# interconnect_RSS_V1_0.net
KiCad netlist of a schematic drawn in EAGLE
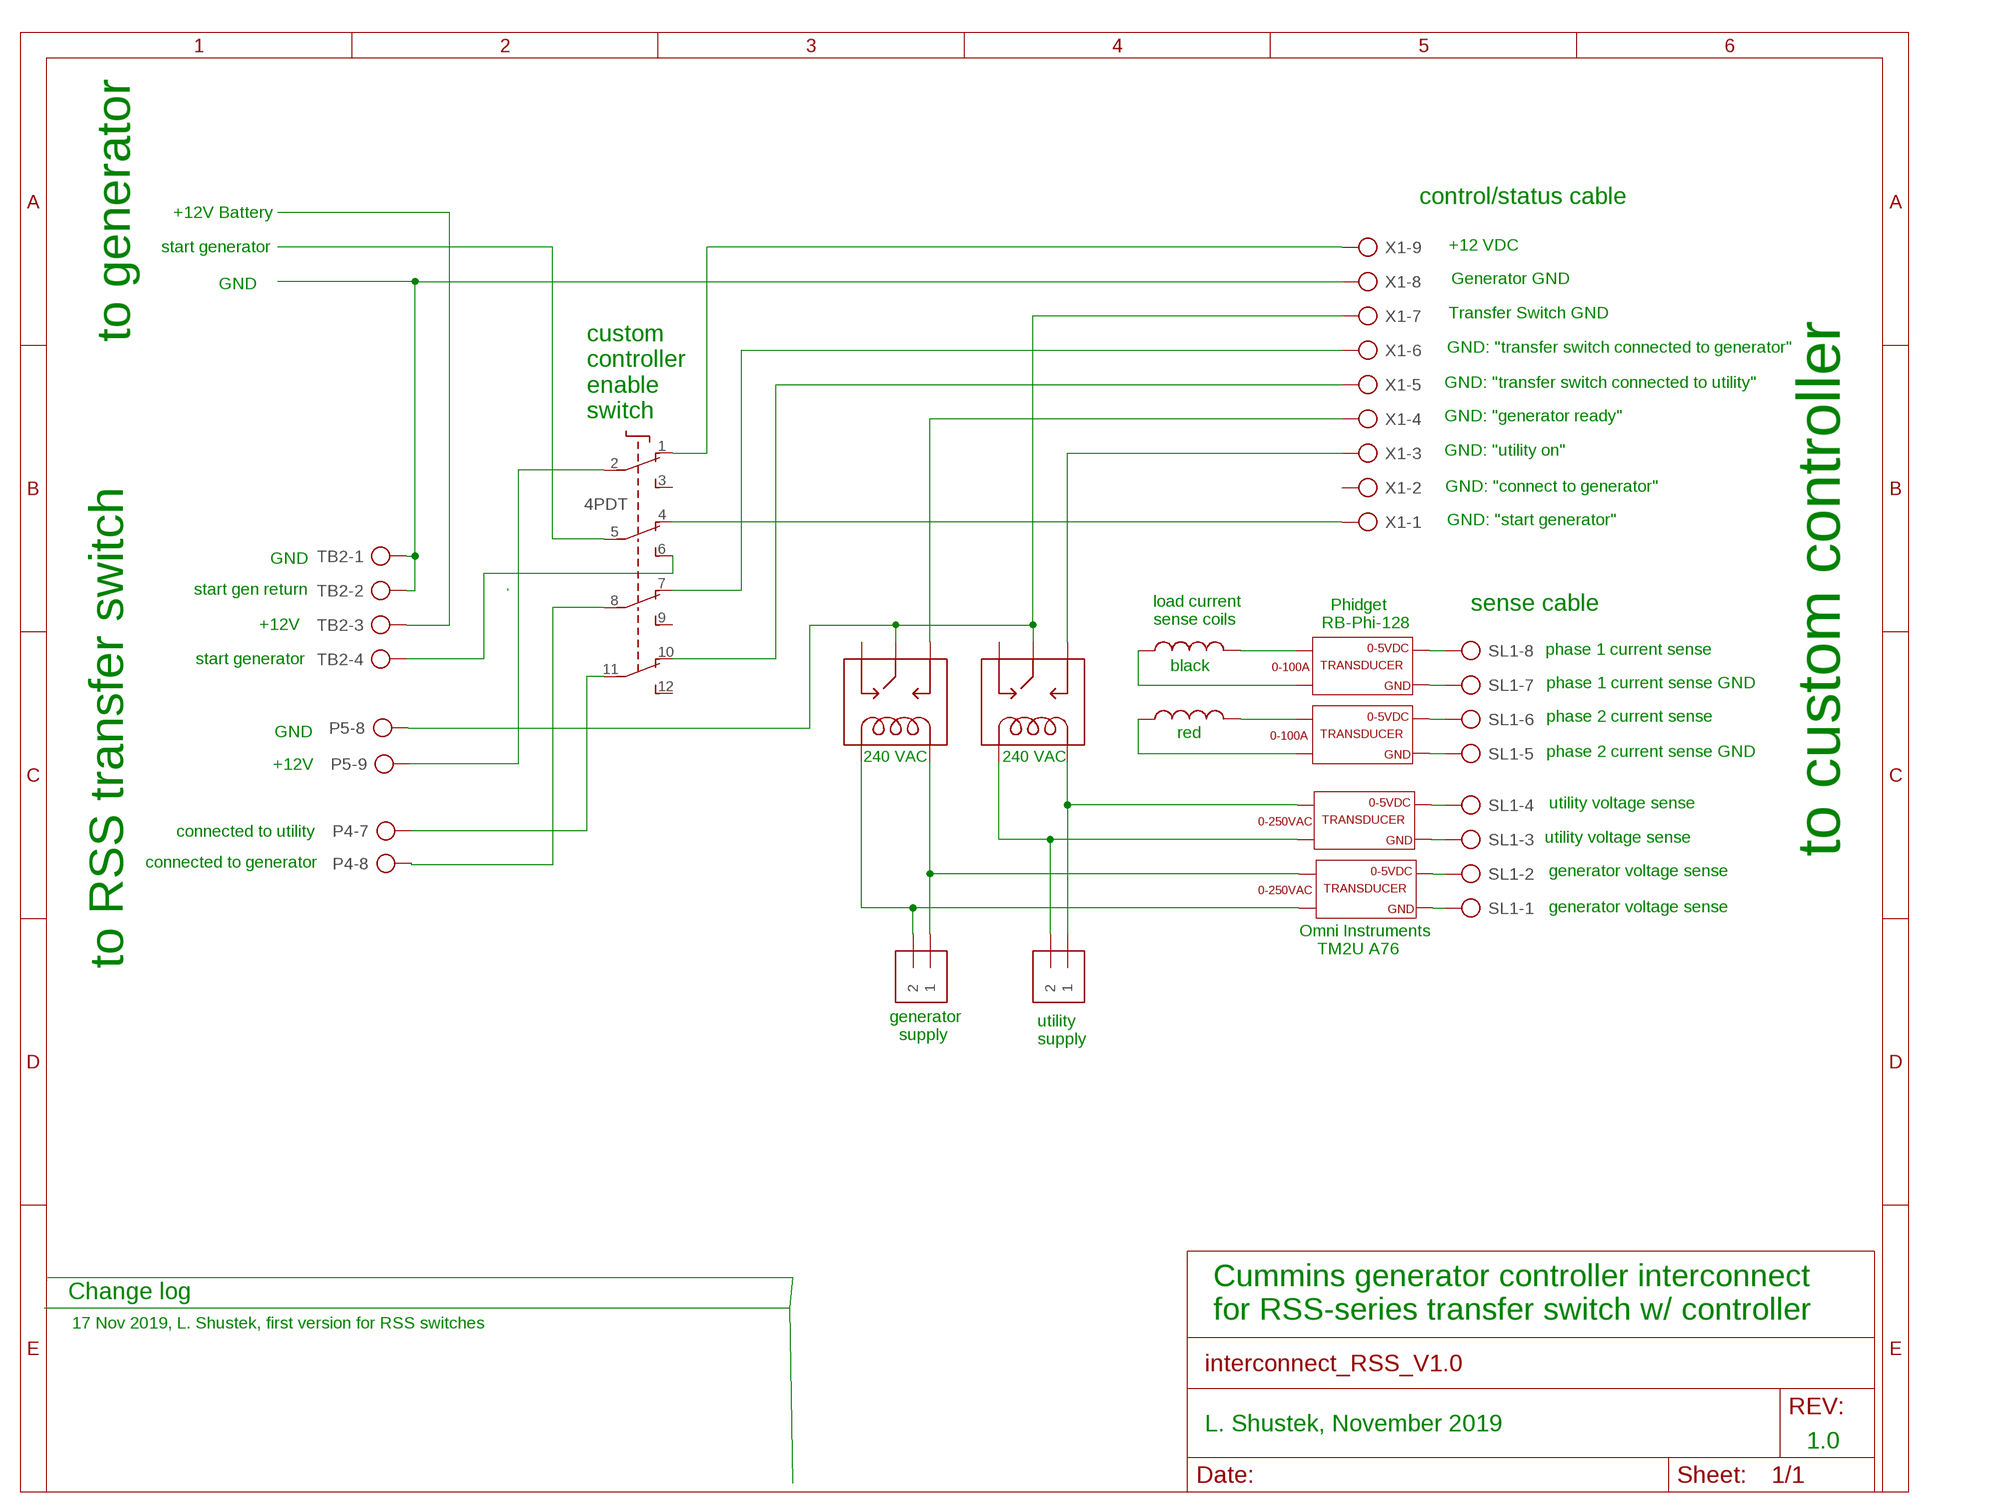
[diagram p0: schematic, sheet 1]

(export (version "E")
  (design (tool "Eeschema 10.0.6"))
  (components
    (comp (ref "J1")
      (value "1X2-3.5MM")
      (footprint "eagle-import:1X2-3.5MM")
      (libsource (lib "eagle-import") (part "1X2-3.5MM"))
    )
    (comp (ref "J2")
      (value "1X2-3.5MM")
      (footprint "eagle-import:1X2-3.5MM")
      (libsource (lib "eagle-import") (part "1X2-3.5MM"))
    )
    (comp (ref "K1")
      (value "RELAY-SPDT-V2")
      (footprint "eagle-import:RELAY-PANASONIC-JS")
      (libsource (lib "eagle-import") (part "RELAY-SPDT-V2"))
    )
    (comp (ref "K2")
      (value "RELAY-SPDT-V2")
      (footprint "eagle-import:RELAY-PANASONIC-JS")
      (libsource (lib "eagle-import") (part "RELAY-SPDT-V2"))
    )
    (comp (ref "L1")
      (value "L-US0204/5")
      (footprint "eagle-import:0204_5")
      (libsource (lib "eagle-import") (part "L-US0204/5"))
    )
    (comp (ref "L2")
      (value "L-US0204/5")
      (footprint "eagle-import:0204_5")
      (libsource (lib "eagle-import") (part "L-US0204/5"))
    )
    (comp (ref "P4")
      (value "AK500/10")
      (footprint "eagle-import:AK500_10")
      (libsource (lib "eagle-import") (part "AK500/10"))
    )
    (comp (ref "P5")
      (value "AK500/10")
      (footprint "eagle-import:AK500_10")
      (libsource (lib "eagle-import") (part "AK500/10"))
    )
    (comp (ref "S2")
      (value "4PDT")
      (footprint "eagle-import:4PDT")
      (libsource (lib "eagle-import") (part "4PDT"))
    )
    (comp (ref "SL1")
      (value "AK500/8")
      (footprint "eagle-import:AK500_8")
      (libsource (lib "eagle-import") (part "AK500/8"))
    )
    (comp (ref "TB2")
      (value "AK500/10")
      (footprint "eagle-import:AK500_10")
      (libsource (lib "eagle-import") (part "AK500/10"))
    )
    (comp (ref "U$1")
      (value "0-100A")
      (footprint "eagle-import:TRANSDUCER")
      (libsource (lib "eagle-import") (part "TRANSDUCER"))
    )
    (comp (ref "U$2")
      (value "0-100A")
      (footprint "eagle-import:TRANSDUCER")
      (libsource (lib "eagle-import") (part "TRANSDUCER"))
    )
    (comp (ref "U$3")
      (value "0-250VAC")
      (footprint "eagle-import:TRANSDUCER")
      (libsource (lib "eagle-import") (part "TRANSDUCER"))
    )
    (comp (ref "U$4")
      (value "0-250VAC")
      (footprint "eagle-import:TRANSDUCER")
      (libsource (lib "eagle-import") (part "TRANSDUCER"))
    )
    (comp (ref "X1")
      (value "AK500/9")
      (footprint "eagle-import:AK500_9")
      (libsource (lib "eagle-import") (part "AK500/9"))
    )
  )
  (nets
    (net (code "1") (name "Net-(K1-COIL1)") (class "Default")
      (node (ref "J1") (pin "2") (pinfunction "2_2") (pintype "passive"))
      (node (ref "K1") (pin "P$2") (pinfunction "COIL1_P$2") (pintype "bidirectional"))
      (node (ref "U$4") (pin "P$2") (pinfunction "P$2_P$2") (pintype "bidirectional"))
    )
    (net (code "2") (name "Net-(K1-COIL2)") (class "Default")
      (node (ref "J1") (pin "1") (pinfunction "1_1") (pintype "passive"))
      (node (ref "K1") (pin "P$5") (pinfunction "COIL2_P$5") (pintype "bidirectional"))
      (node (ref "U$4") (pin "P$1") (pinfunction "P$1_P$1") (pintype "bidirectional"))
    )
    (net (code "3") (name "Net-(K1-MAIN)") (class "Default")
      (node (ref "K1") (pin "P$1") (pinfunction "MAIN_P$1") (pintype "bidirectional"))
      (node (ref "K2") (pin "P$1") (pinfunction "MAIN_P$1") (pintype "bidirectional"))
      (node (ref "P5") (pin "8") (pinfunction "KL_8") (pintype "passive"))
      (node (ref "X1") (pin "7") (pinfunction "KL_7") (pintype "passive"))
    )
    (net (code "4") (name "Net-(K1-NO)") (class "Default")
      (node (ref "K1") (pin "P$3") (pinfunction "NO_P$3") (pintype "bidirectional"))
      (node (ref "X1") (pin "4") (pinfunction "KL_4") (pintype "passive"))
    )
    (net (code "5") (name "Net-(K2-COIL1)") (class "Default")
      (node (ref "J2") (pin "2") (pinfunction "2_2") (pintype "passive"))
      (node (ref "K2") (pin "P$2") (pinfunction "COIL1_P$2") (pintype "bidirectional"))
      (node (ref "U$3") (pin "P$2") (pinfunction "P$2_P$2") (pintype "bidirectional"))
    )
    (net (code "6") (name "Net-(K2-COIL2)") (class "Default")
      (node (ref "J2") (pin "1") (pinfunction "1_1") (pintype "passive"))
      (node (ref "K2") (pin "P$5") (pinfunction "COIL2_P$5") (pintype "bidirectional"))
      (node (ref "U$3") (pin "P$1") (pinfunction "P$1_P$1") (pintype "bidirectional"))
    )
    (net (code "7") (name "Net-(K2-NO)") (class "Default")
      (node (ref "K2") (pin "P$3") (pinfunction "NO_P$3") (pintype "bidirectional"))
      (node (ref "X1") (pin "3") (pinfunction "KL_3") (pintype "passive"))
    )
    (net (code "8") (name "Net-(L1-Pad1)") (class "Default")
      (node (ref "L1") (pin "1") (pinfunction "1_1") (pintype "passive"))
      (node (ref "U$1") (pin "P$2") (pinfunction "P$2_P$2") (pintype "bidirectional"))
    )
    (net (code "9") (name "Net-(L1-Pad2)") (class "Default")
      (node (ref "L1") (pin "2") (pinfunction "2_2") (pintype "passive"))
      (node (ref "U$1") (pin "P$1") (pinfunction "P$1_P$1") (pintype "bidirectional"))
    )
    (net (code "10") (name "Net-(L2-Pad1)") (class "Default")
      (node (ref "L2") (pin "1") (pinfunction "1_1") (pintype "passive"))
      (node (ref "U$2") (pin "P$2") (pinfunction "P$2_P$2") (pintype "bidirectional"))
    )
    (net (code "11") (name "Net-(L2-Pad2)") (class "Default")
      (node (ref "L2") (pin "2") (pinfunction "2_2") (pintype "passive"))
      (node (ref "U$2") (pin "P$1") (pinfunction "P$1_P$1") (pintype "bidirectional"))
    )
    (net (code "12") (name "Net-(P4H-KL)") (class "Default")
      (node (ref "P4") (pin "7") (pinfunction "KL_7") (pintype "passive"))
      (node (ref "S2") (pin "11") (pinfunction "P4_11") (pintype "passive"))
    )
    (net (code "13") (name "Net-(P4I-KL)") (class "Default")
      (node (ref "P4") (pin "8") (pinfunction "KL_8") (pintype "passive"))
      (node (ref "S2") (pin "8") (pinfunction "P3_8") (pintype "passive"))
    )
    (net (code "14") (name "Net-(P5J-KL)") (class "Default")
      (node (ref "P5") (pin "9") (pinfunction "KL_9") (pintype "passive"))
      (node (ref "S2") (pin "2") (pinfunction "P1_2") (pintype "passive"))
    )
    (net (code "15") (name "Net-(S2-O1)") (class "Default")
      (node (ref "S2") (pin "1") (pinfunction "O1_1") (pintype "passive"))
      (node (ref "X1") (pin "9") (pinfunction "KL_9") (pintype "passive"))
    )
    (net (code "16") (name "Net-(S2-O2)") (class "Default")
      (node (ref "S2") (pin "4") (pinfunction "O2_4") (pintype "passive"))
      (node (ref "X1") (pin "1") (pinfunction "KL_1") (pintype "passive"))
    )
    (net (code "17") (name "Net-(S2-O3)") (class "Default")
      (node (ref "S2") (pin "7") (pinfunction "O3_7") (pintype "passive"))
      (node (ref "X1") (pin "6") (pinfunction "KL_6") (pintype "passive"))
    )
    (net (code "18") (name "Net-(S2-O4)") (class "Default")
      (node (ref "S2") (pin "10") (pinfunction "O4_10") (pintype "passive"))
      (node (ref "X1") (pin "5") (pinfunction "KL_5") (pintype "passive"))
    )
    (net (code "19") (name "Net-(S2-S2)") (class "Default")
      (node (ref "S2") (pin "6") (pinfunction "S2_6") (pintype "passive"))
      (node (ref "TB2") (pin "4") (pinfunction "KL_4") (pintype "passive"))
    )
    (net (code "20") (name "Net-(SL1A-KL)") (class "Default")
      (node (ref "SL1") (pin "1") (pinfunction "KL_1") (pintype "passive"))
      (node (ref "U$4") (pin "P$4") (pinfunction "P$4_P$4") (pintype "bidirectional"))
    )
    (net (code "21") (name "Net-(SL1B-KL)") (class "Default")
      (node (ref "SL1") (pin "2") (pinfunction "KL_2") (pintype "passive"))
      (node (ref "U$4") (pin "P$3") (pinfunction "P$3_P$3") (pintype "bidirectional"))
    )
    (net (code "22") (name "Net-(SL1C-KL)") (class "Default")
      (node (ref "SL1") (pin "3") (pinfunction "KL_3") (pintype "passive"))
      (node (ref "U$3") (pin "P$4") (pinfunction "P$4_P$4") (pintype "bidirectional"))
    )
    (net (code "23") (name "Net-(SL1D-KL)") (class "Default")
      (node (ref "SL1") (pin "4") (pinfunction "KL_4") (pintype "passive"))
      (node (ref "U$3") (pin "P$3") (pinfunction "P$3_P$3") (pintype "bidirectional"))
    )
    (net (code "24") (name "Net-(SL1E-KL)") (class "Default")
      (node (ref "SL1") (pin "5") (pinfunction "KL_5") (pintype "passive"))
      (node (ref "U$2") (pin "P$4") (pinfunction "P$4_P$4") (pintype "bidirectional"))
    )
    (net (code "25") (name "Net-(SL1F-KL)") (class "Default")
      (node (ref "SL1") (pin "6") (pinfunction "KL_6") (pintype "passive"))
      (node (ref "U$2") (pin "P$3") (pinfunction "P$3_P$3") (pintype "bidirectional"))
    )
    (net (code "26") (name "Net-(SL1G-KL)") (class "Default")
      (node (ref "SL1") (pin "7") (pinfunction "KL_7") (pintype "passive"))
      (node (ref "U$1") (pin "P$4") (pinfunction "P$4_P$4") (pintype "bidirectional"))
    )
    (net (code "27") (name "Net-(SL1H-KL)") (class "Default")
      (node (ref "SL1") (pin "8") (pinfunction "KL_8") (pintype "passive"))
      (node (ref "U$1") (pin "P$3") (pinfunction "P$3_P$3") (pintype "bidirectional"))
    )
    (net (code "28") (name "Net-(TB2A-KL)") (class "Default")
      (node (ref "TB2") (pin "1") (pinfunction "KL_1") (pintype "passive"))
      (node (ref "TB2") (pin "2") (pinfunction "KL_2") (pintype "passive"))
      (node (ref "X1") (pin "8") (pinfunction "KL_8") (pintype "passive"))
    )
    (net (code "29") (name "unconnected-(K1-NC-PadP$4)") (class "Default")
      (node (ref "K1") (pin "P$4") (pinfunction "NC_P$4") (pintype "bidirectional"))
    )
    (net (code "30") (name "unconnected-(K2-NC-PadP$4)") (class "Default")
      (node (ref "K2") (pin "P$4") (pinfunction "NC_P$4") (pintype "bidirectional"))
    )
    (net (code "31") (name "unconnected-(S2-P2-Pad5)") (class "Default")
      (node (ref "S2") (pin "5") (pinfunction "P2_5") (pintype "passive"))
    )
    (net (code "32") (name "unconnected-(S2-S1-Pad3)") (class "Default")
      (node (ref "S2") (pin "3") (pinfunction "S1_3") (pintype "passive"))
    )
    (net (code "33") (name "unconnected-(S2-S3-Pad9)") (class "Default")
      (node (ref "S2") (pin "9") (pinfunction "S3_9") (pintype "passive"))
    )
    (net (code "34") (name "unconnected-(S2-S4-Pad12)") (class "Default")
      (node (ref "S2") (pin "12") (pinfunction "S4_12") (pintype "passive"))
    )
    (net (code "35") (name "unconnected-(TB2D-KL-Pad3)") (class "Default")
      (node (ref "TB2") (pin "3") (pinfunction "KL_3") (pintype "passive"))
    )
    (net (code "36") (name "unconnected-(X1B-KL-Pad2)") (class "Default")
      (node (ref "X1") (pin "2") (pinfunction "KL_2") (pintype "passive"))
    )
  )
)
